# TopLevel.net
KiCad netlist of a schematic drawn in Altium Designer
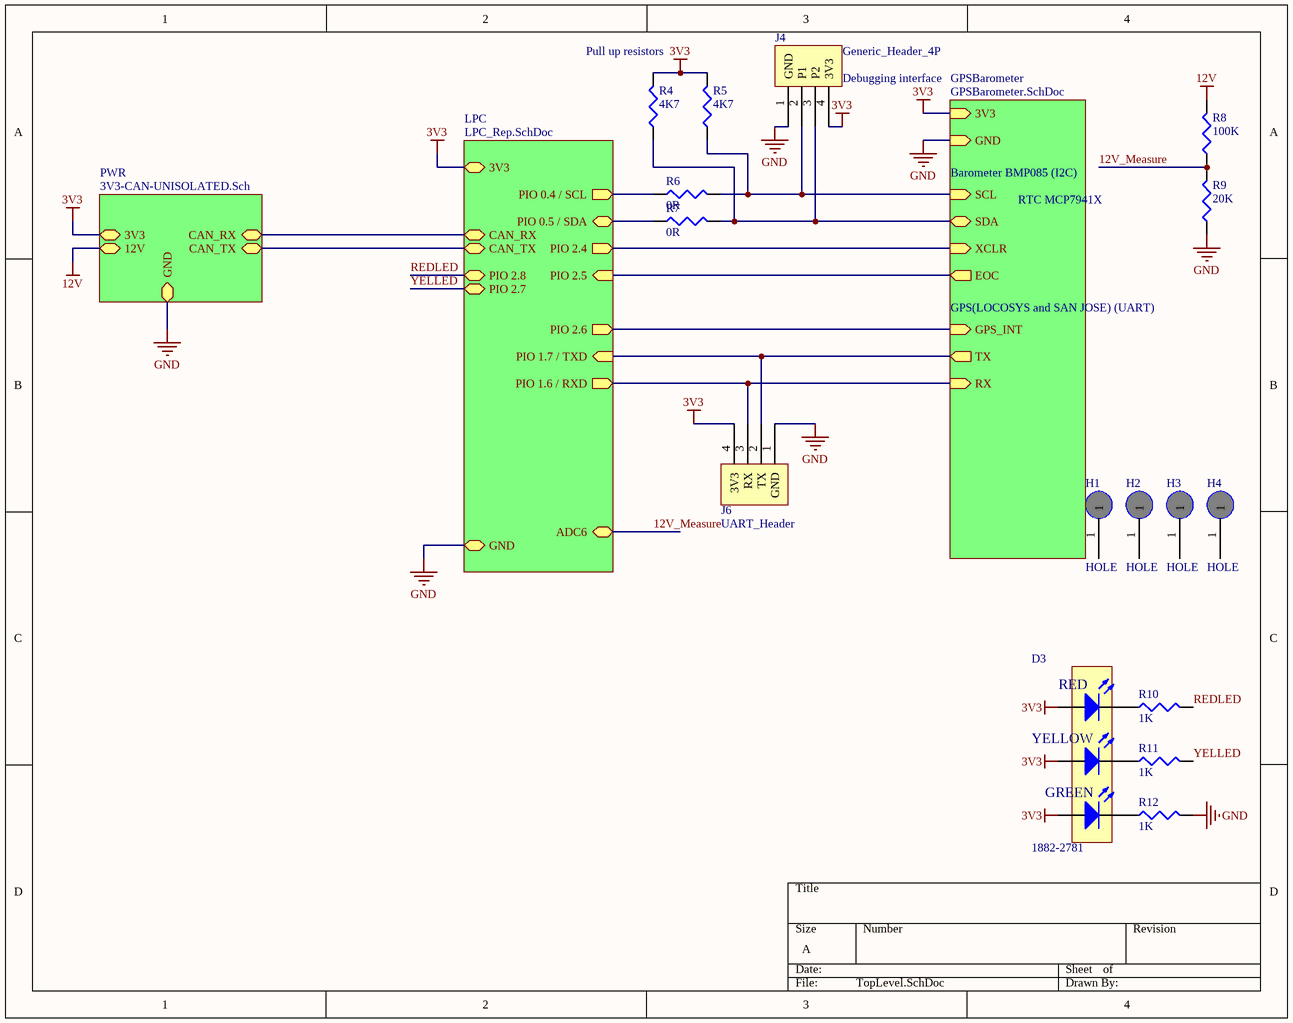
[diagram p0: TopLevel.SchDoc]

(export (version "E")
  (design (tool "Eeschema 10.0.6"))
  (components
    (comp (ref "D3")
      (value "1882-2781")
      (footprint "LED_TRILEVEL")
      (description "Three level LED")
      (libsource (lib "RCLDQ") (part "LED-TRILEVEL"))
    )
    (comp (ref "H1")
      (value "HOLE")
      (footprint "M2.5")
      (description "Hole")
      (libsource (lib "Miscellaneous") (part "HOLE"))
    )
    (comp (ref "H2")
      (value "HOLE")
      (footprint "M2.5")
      (description "Hole")
      (libsource (lib "Miscellaneous") (part "HOLE"))
    )
    (comp (ref "H3")
      (value "HOLE")
      (footprint "M2.5")
      (description "Hole")
      (libsource (lib "Miscellaneous") (part "HOLE"))
    )
    (comp (ref "H4")
      (value "HOLE")
      (footprint "M2.5")
      (description "Hole")
      (libsource (lib "Miscellaneous") (part "HOLE"))
    )
    (comp (ref "J4")
      (value "Generic_Header_4P")
      (footprint "IDC4")
      (libsource (lib "2009_BatteryMaster") (part "Generic_Header_4P"))
    )
    (comp (ref "J6")
      (value "UART_Header")
      (footprint "IDC4")
      (libsource (lib "2009_BatteryMaster") (part "UART_Header"))
    )
    (comp (ref "R4")
      (value "4K7")
      (footprint "0603")
      (description "Resistor")
      (libsource (lib "RCLDQ") (part "RES1"))
    )
    (comp (ref "R5")
      (value "4K7")
      (footprint "0603")
      (description "Resistor")
      (libsource (lib "RCLDQ") (part "RES1"))
    )
    (comp (ref "R6")
      (value "0R")
      (footprint "0603")
      (description "Resistor")
      (libsource (lib "2009_BatteryMaster") (part "RES1"))
    )
    (comp (ref "R7")
      (value "0R")
      (footprint "0603")
      (description "Resistor")
      (libsource (lib "2009_BatteryMaster") (part "RES1"))
    )
    (comp (ref "R8")
      (value "100K")
      (footprint "0603")
      (description "Resistor")
      (libsource (lib "2009_BatteryMaster") (part "RES1"))
    )
    (comp (ref "R9")
      (value "20K")
      (footprint "0603")
      (description "Resistor")
      (libsource (lib "2009_BatteryMaster") (part "RES1"))
    )
    (comp (ref "R10")
      (value "1K")
      (footprint "0603")
      (description "Resistor")
      (libsource (lib "RCLDQ") (part "RES1"))
    )
    (comp (ref "R11")
      (value "1K")
      (footprint "0603")
      (description "Resistor")
      (libsource (lib "RCLDQ") (part "RES1"))
    )
    (comp (ref "R12")
      (value "1K")
      (footprint "0603")
      (description "Resistor")
      (libsource (lib "RCLDQ") (part "RES1"))
    )
  )
  (nets
    (net (code "1") (name "/12V_Measure") (class "Default")
      (node (ref "R8") (pin "1") (pinfunction "1_1") (pintype "passive"))
      (node (ref "R9") (pin "2") (pinfunction "2_2") (pintype "passive"))
    )
    (net (code "5") (name "/PIO 0.4 {slash} SCL") (class "Default")
      (node (ref "R6") (pin "1") (pinfunction "1_1") (pintype "passive"))
    )
    (net (code "6") (name "/PIO 0.5 {slash} SDA") (class "Default")
      (node (ref "R7") (pin "1") (pinfunction "1_1") (pintype "passive"))
    )
    (net (code "7") (name "/PIO 1.6 {slash} RXD") (class "Default")
      (node (ref "J6") (pin "3") (pinfunction "RX_3") (pintype "passive"))
    )
    (net (code "10") (name "/REDLED") (class "Default")
      (node (ref "R10") (pin "2") (pinfunction "2_2") (pintype "passive"))
    )
    (net (code "11") (name "/SCL") (class "Default")
      (node (ref "J4") (pin "2") (pinfunction "P1_2") (pintype "passive"))
      (node (ref "R5") (pin "1") (pinfunction "1_1") (pintype "passive"))
      (node (ref "R6") (pin "2") (pinfunction "2_2") (pintype "passive"))
    )
    (net (code "12") (name "/SDA") (class "Default")
      (node (ref "J4") (pin "3") (pinfunction "P2_3") (pintype "passive"))
      (node (ref "R4") (pin "1") (pinfunction "1_1") (pintype "passive"))
      (node (ref "R7") (pin "2") (pinfunction "2_2") (pintype "passive"))
    )
    (net (code "13") (name "/TX") (class "Default")
      (node (ref "J6") (pin "2") (pinfunction "TX_2") (pintype "passive"))
    )
    (net (code "14") (name "/YELLED") (class "Default")
      (node (ref "R11") (pin "2") (pinfunction "2_2") (pintype "passive"))
    )
    (net (code "15") (name "3V3") (class "Default")
      (node (ref "D3") (pin "4") (pinfunction "A_4") (pintype "passive"))
      (node (ref "D3") (pin "5") (pinfunction "A_5") (pintype "passive"))
      (node (ref "D3") (pin "6") (pinfunction "A_6") (pintype "passive"))
      (node (ref "J4") (pin "4") (pinfunction "3V3_4") (pintype "passive"))
      (node (ref "J6") (pin "4") (pinfunction "3V3_4") (pintype "passive"))
      (node (ref "R4") (pin "2") (pinfunction "2_2") (pintype "passive"))
      (node (ref "R5") (pin "2") (pinfunction "2_2") (pintype "passive"))
    )
    (net (code "16") (name "12V") (class "Default")
      (node (ref "R8") (pin "2") (pinfunction "2_2") (pintype "passive"))
    )
    (net (code "17") (name "GND") (class "Default")
      (node (ref "J4") (pin "1") (pinfunction "GND_1") (pintype "passive"))
      (node (ref "J6") (pin "1") (pinfunction "GND_1") (pintype "passive"))
      (node (ref "R12") (pin "2") (pinfunction "2_2") (pintype "passive"))
      (node (ref "R9") (pin "1") (pinfunction "1_1") (pintype "passive"))
    )
    (net (code "18") (name "Net-(D3-K-Pad1)") (class "Default")
      (node (ref "D3") (pin "1") (pinfunction "K_1") (pintype "passive"))
      (node (ref "R12") (pin "1") (pinfunction "1_1") (pintype "passive"))
    )
    (net (code "19") (name "Net-(D3-K-Pad2)") (class "Default")
      (node (ref "D3") (pin "2") (pinfunction "K_2") (pintype "passive"))
      (node (ref "R11") (pin "1") (pinfunction "1_1") (pintype "passive"))
    )
    (net (code "20") (name "Net-(D3-K-Pad3)") (class "Default")
      (node (ref "D3") (pin "3") (pinfunction "K_3") (pintype "passive"))
      (node (ref "R10") (pin "1") (pinfunction "1_1") (pintype "passive"))
    )
    (net (code "21") (name "unconnected-(H1-Pad1)") (class "Default")
      (node (ref "H1") (pin "1") (pinfunction "1_1") (pintype "passive"))
    )
    (net (code "22") (name "unconnected-(H2-Pad1)") (class "Default")
      (node (ref "H2") (pin "1") (pinfunction "1_1") (pintype "passive"))
    )
    (net (code "23") (name "unconnected-(H3-Pad1)") (class "Default")
      (node (ref "H3") (pin "1") (pinfunction "1_1") (pintype "passive"))
    )
    (net (code "24") (name "unconnected-(H4-Pad1)") (class "Default")
      (node (ref "H4") (pin "1") (pinfunction "1_1") (pintype "passive"))
    )
  )
)
